# DM1092_QWIIC.net
KiCad netlist of a schematic drawn in Altium Designer
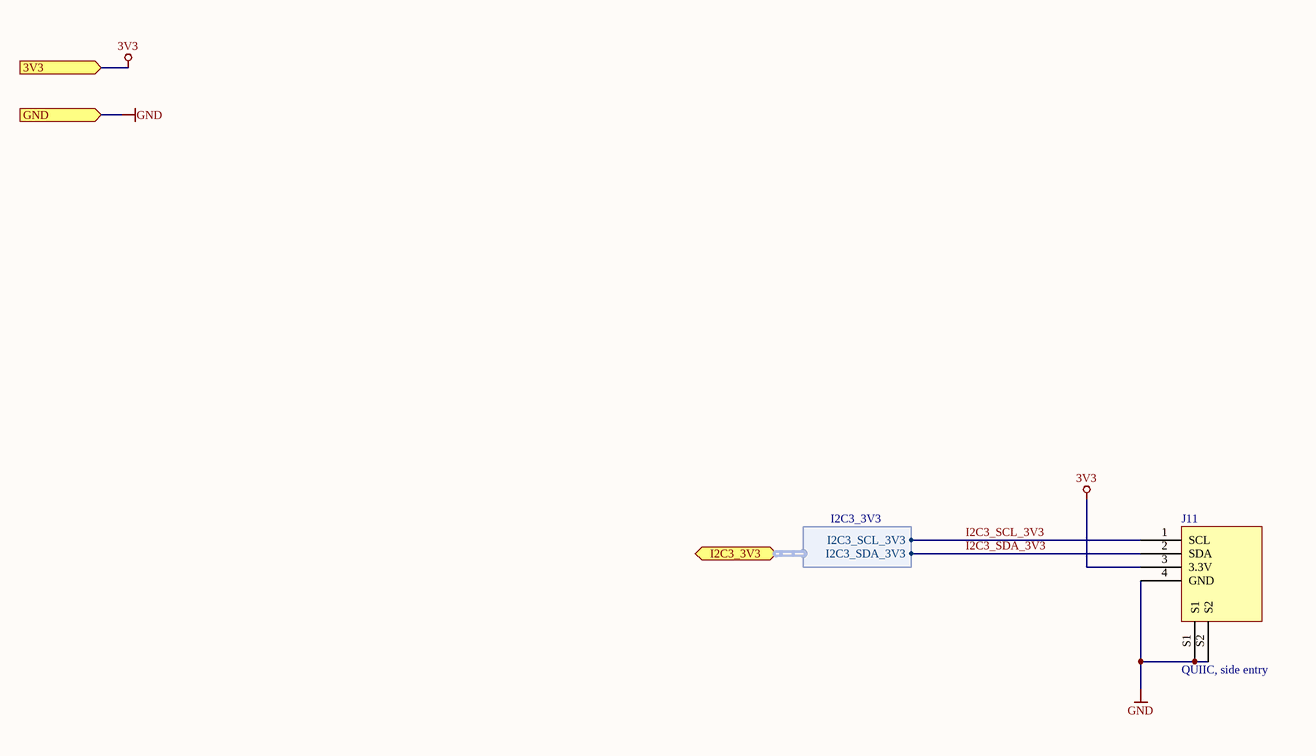
[diagram p0: DM1092_QWIIC.SchDoc]

(export (version "E")
  (design (tool "Eeschema 10.0.6"))
  (components
    (comp (ref "J11")
      (value "QUIIC, side entry")
      (footprint "BW1092_R0M0E0:SM04B-SRSS-TB(LF)(SN)")
      (description "Connector Header, Side Entry, SR Series, 4 Position, 1.00mm, 50V, Surface Mount, Tin, Natural")
      (libsource (lib "DM1092_R0M0E0") (part "SM04B-SRSS-TB(LF)(SN)"))
    )
  )
  (nets
    (net (code "2") (name "/I2C3_SCL_3V3") (class "Default")
      (node (ref "J11") (pin "1") (pinfunction "SCL_1") (pintype "passive"))
    )
    (net (code "3") (name "/I2C3_SDA_3V3") (class "Default")
      (node (ref "J11") (pin "2") (pinfunction "SDA_2") (pintype "passive"))
    )
    (net (code "5") (name "3V3") (class "Default")
      (node (ref "J11") (pin "3") (pinfunction "3.3V_3") (pintype "passive"))
    )
    (net (code "6") (name "GND") (class "Default")
      (node (ref "J11") (pin "4") (pinfunction "GND_4") (pintype "passive"))
      (node (ref "J11") (pin "S1") (pinfunction "S1_S1") (pintype "passive"))
      (node (ref "J11") (pin "S2") (pinfunction "S2_S2") (pintype "passive"))
    )
  )
)
